# tinyusbboard.net
KiCad netlist of a schematic drawn in Altium Designer
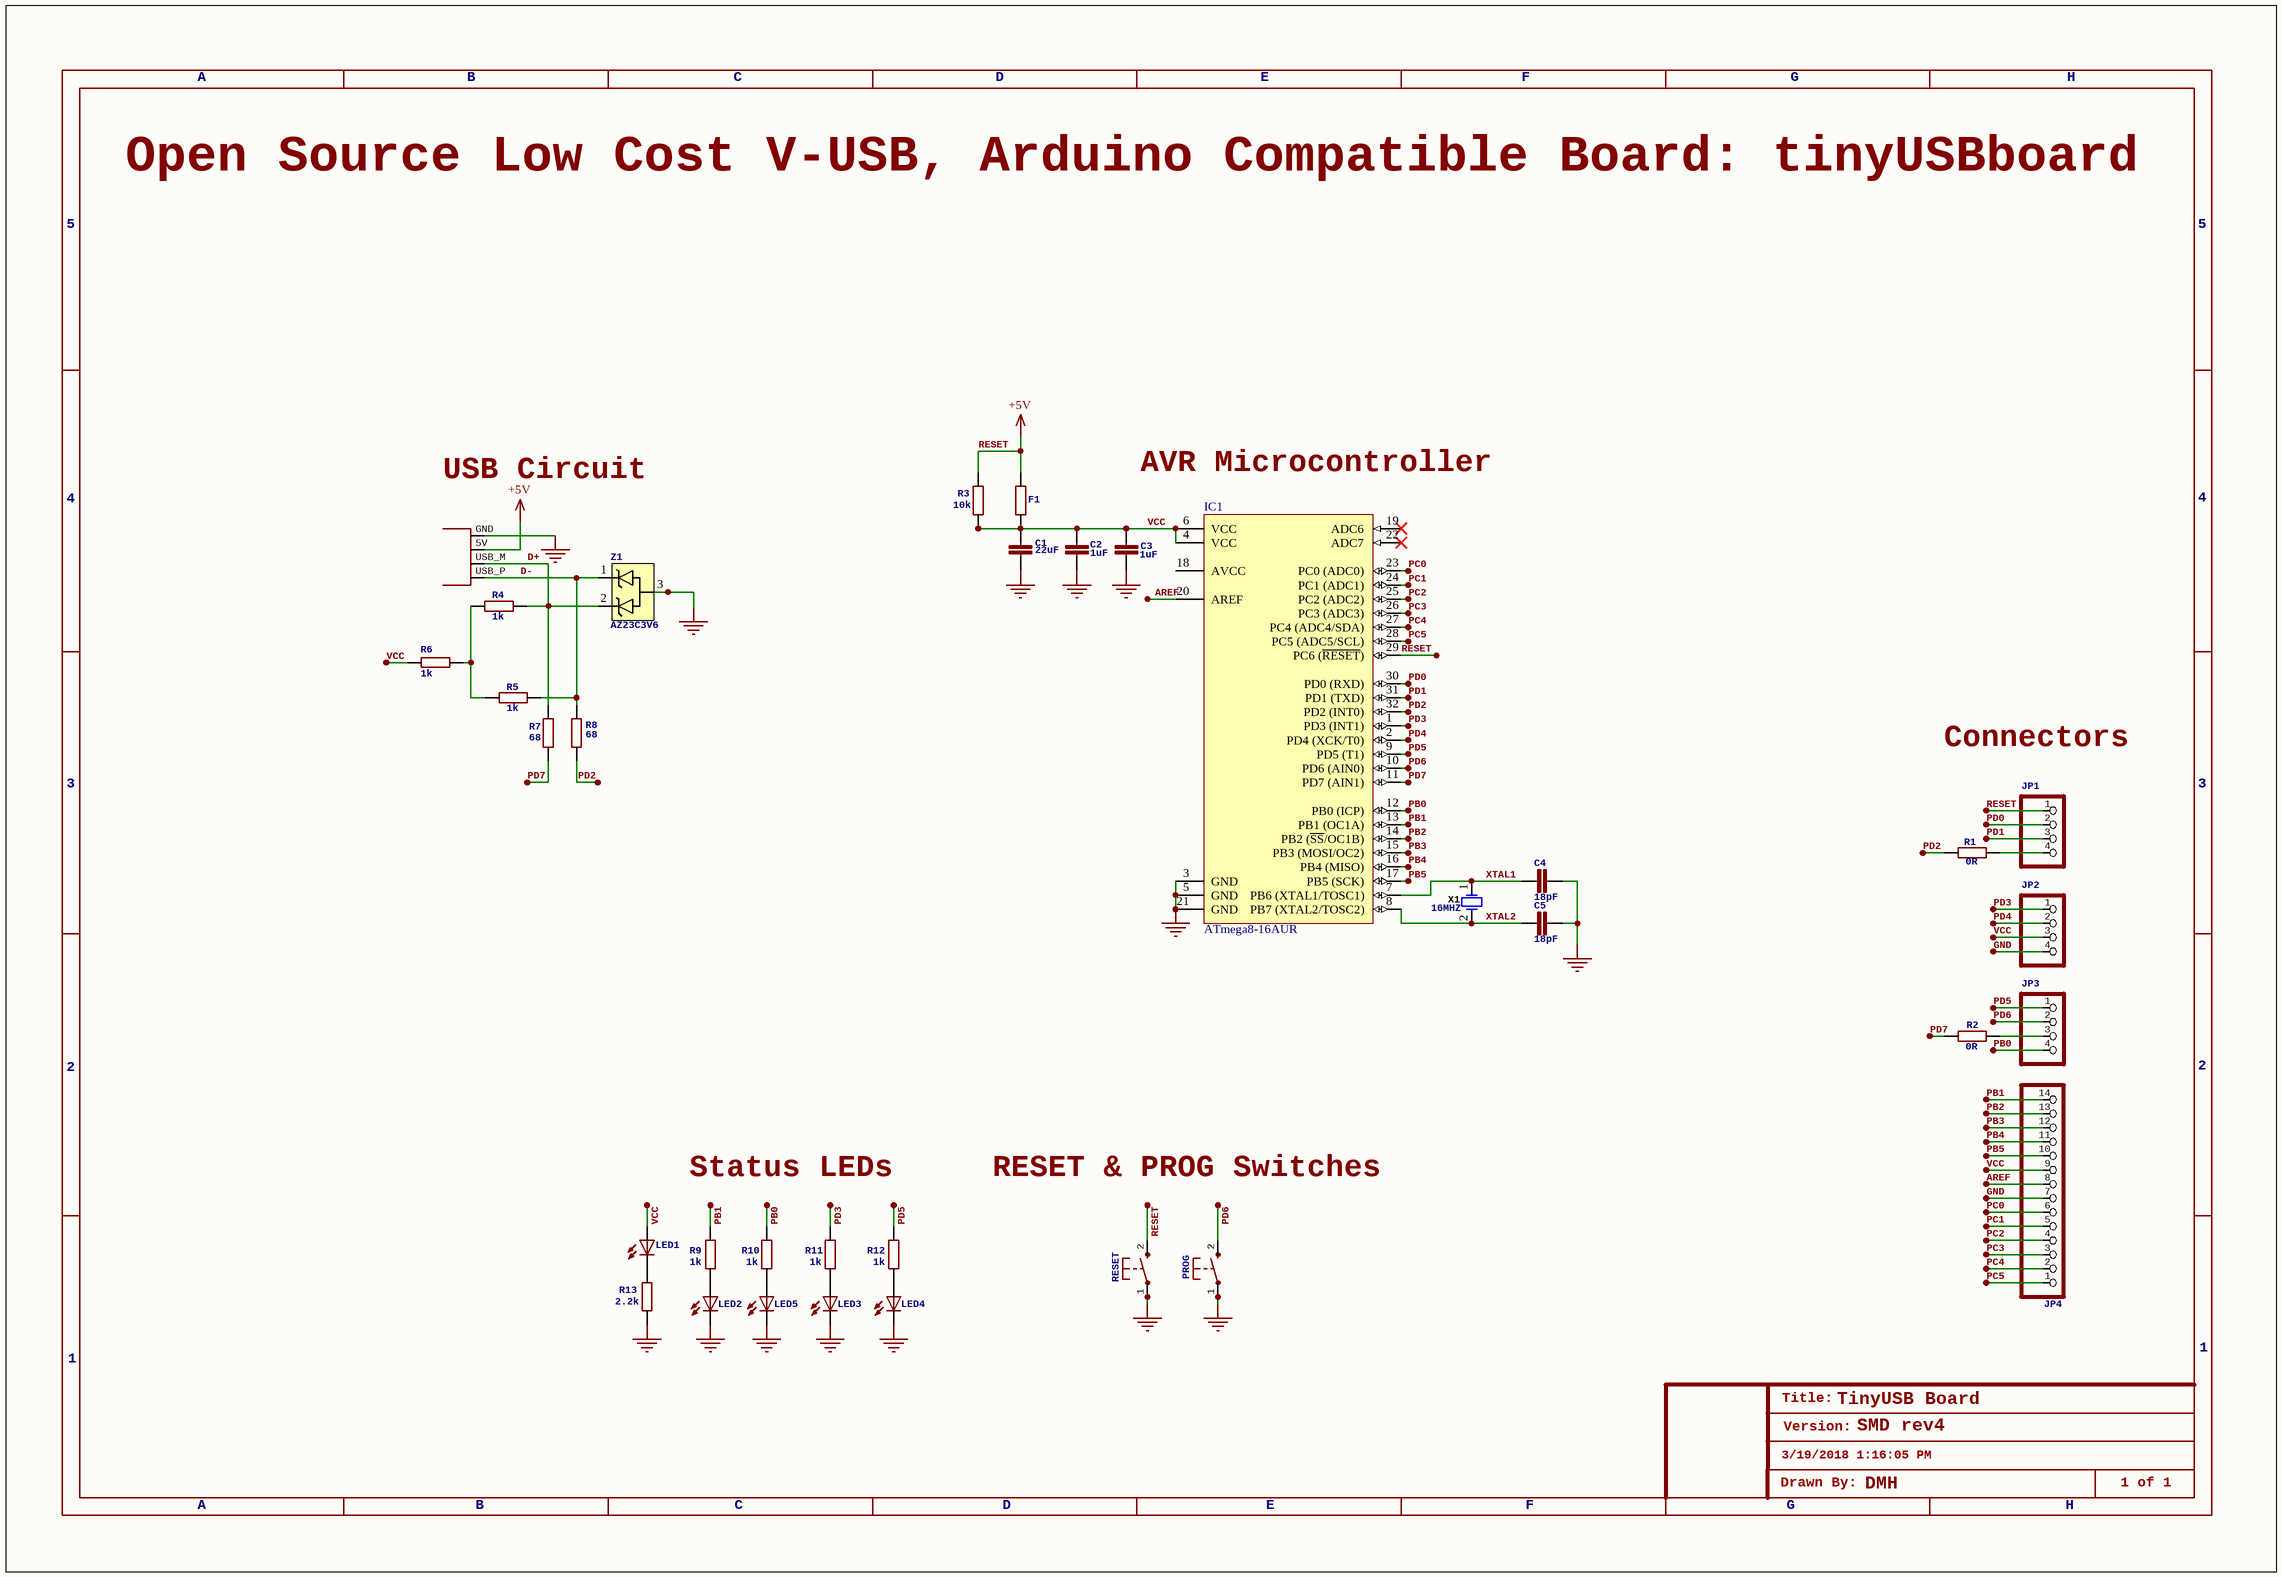
[diagram p0: tinyusbboard.SchDoc]

(export (version "E")
  (design (tool "Eeschema 10.0.6"))
  (components
    (comp (ref "C1")
      (value "22uF")
      (footprint "C1206K")
      (description "CAPACITOR, European symbol")
      (libsource (lib "resistor") (part "C-EUC1206K"))
    )
    (comp (ref "C2")
      (value "1uF")
      (footprint "C0805")
      (description "CAPACITOR, European symbol")
      (libsource (lib "") (part "C-EUC0805K_1"))
    )
    (comp (ref "C3")
      (value "1uF")
      (footprint "C0805")
      (description "CAPACITOR, European symbol")
      (libsource (lib "") (part "C-EUC0805K_1"))
    )
    (comp (ref "C4")
      (value "18pF")
      (footprint "C0805")
      (description "CAPACITOR, European symbol")
      (libsource (lib "resistor") (part "C-EUC0805K"))
    )
    (comp (ref "C5")
      (value "18pF")
      (footprint "C0805")
      (description "CAPACITOR, European symbol")
      (libsource (lib "resistor") (part "C-EUC0805K"))
    )
    (comp (ref "F1")
      (value "0")
      (footprint "R1206W")
      (description "RESISTOR, European symbol")
      (libsource (lib "resistor") (part "R-EU_R1206W"))
    )
    (comp (ref "IC1")
      (value "ATmega8-16AUR")
      (footprint "32A_M")
      (libsource (lib "Altium Content Vault") (part "MC-8B-AT8L-SQ32A"))
    )
    (comp (ref "JP1")
      (value "PINHD-1X4")
      (footprint "4P Jumper")
      (description "PIN HEADER")
      (libsource (lib "pinhead") (part "PINHD-1X4"))
    )
    (comp (ref "JP2")
      (value "PINHD-1X4")
      (footprint "4P Jumper")
      (description "PIN HEADER")
      (libsource (lib "pinhead") (part "PINHD-1X4"))
    )
    (comp (ref "JP3")
      (value "PINHD-1X4")
      (footprint "4P Jumper")
      (description "PIN HEADER")
      (libsource (lib "pinhead") (part "PINHD-1X4"))
    )
    (comp (ref "JP4")
      (value "PINHD-1X14")
      (footprint "124P Jumper")
      (description "PIN HEADER")
      (libsource (lib "pinhead") (part "PINHD-1X14"))
    )
    (comp (ref "LED1")
      (value "POWER")
      (footprint "LED_1206_2")
      (libsource (lib "led") (part "LEDCHIPLED_0805"))
    )
    (comp (ref "LED2")
      (value "red")
      (footprint "LED_1206_2")
      (libsource (lib "led") (part "LEDCHIPLED_0805"))
    )
    (comp (ref "LED3")
      (value "red")
      (footprint "LED_1206_2")
      (libsource (lib "led") (part "LEDCHIPLED_0805"))
    )
    (comp (ref "LED4")
      (value "red")
      (footprint "LED_1206_2")
      (libsource (lib "led") (part "LEDCHIPLED_0805"))
    )
    (comp (ref "LED5")
      (value "red")
      (footprint "LED_1206_2")
      (libsource (lib "led") (part "LEDCHIPLED_0805"))
    )
    (comp (ref "PROG")
      (value "KSS-2EG4430")
      (footprint "KSS-2EG4430")
      (libsource (lib "buttons") (part "KSS-2EG4430"))
    )
    (comp (ref "R1")
      (value "0R")
      (footprint "RESC0805(2012)_M")
      (description "RESISTOR, European symbol")
      (libsource (lib "resistor") (part "R-EU_R0805W"))
    )
    (comp (ref "R2")
      (value "0R")
      (footprint "RESC0805(2012)_M")
      (description "RESISTOR, European symbol")
      (libsource (lib "resistor") (part "R-EU_R0805W"))
    )
    (comp (ref "R3")
      (value "10k")
      (footprint "RESC0805(2012)_M")
      (description "RESISTOR, European symbol")
      (libsource (lib "resistor") (part "R-EU_R0805W"))
    )
    (comp (ref "R4")
      (value "1k")
      (footprint "RESC0805(2012)_M")
      (description "RESISTOR, European symbol")
      (libsource (lib "resistor") (part "R-EU_R0805W"))
    )
    (comp (ref "R5")
      (value "1k")
      (footprint "RESC0805(2012)_M")
      (description "RESISTOR, European symbol")
      (libsource (lib "resistor") (part "R-EU_R0805W"))
    )
    (comp (ref "R6")
      (value "1k")
      (footprint "RESC0805(2012)_M")
      (description "RESISTOR, European symbol")
      (libsource (lib "resistor") (part "R-EU_R0805W"))
    )
    (comp (ref "R7")
      (value "68")
      (footprint "RESC0805(2012)_M")
      (description "RESISTOR, European symbol")
      (libsource (lib "resistor") (part "R-EU_R0805W"))
    )
    (comp (ref "R8")
      (value "68")
      (footprint "RESC0805(2012)_M")
      (description "RESISTOR, European symbol")
      (libsource (lib "resistor") (part "R-EU_R0805W"))
    )
    (comp (ref "R9")
      (value "1k")
      (footprint "RESC0805(2012)_M")
      (description "RESISTOR, European symbol")
      (libsource (lib "resistor") (part "R-EU_R0805W"))
    )
    (comp (ref "R10")
      (value "1k")
      (footprint "RESC0805(2012)_M")
      (description "RESISTOR, European symbol")
      (libsource (lib "resistor") (part "R-EU_R0805W"))
    )
    (comp (ref "R11")
      (value "1k")
      (footprint "RESC0805(2012)_M")
      (description "RESISTOR, European symbol")
      (libsource (lib "resistor") (part "R-EU_R0805W"))
    )
    (comp (ref "R12")
      (value "1k")
      (footprint "RESC0805(2012)_M")
      (description "RESISTOR, European symbol")
      (libsource (lib "resistor") (part "R-EU_R0805W"))
    )
    (comp (ref "R13")
      (value "2.2k")
      (footprint "RESC0805(2012)_M")
      (description "RESISTOR, European symbol")
      (libsource (lib "resistor") (part "R-EU_R0805W"))
    )
    (comp (ref "RESET")
      (value "KSS-2EG4430")
      (footprint "KSS-2EG4430")
      (libsource (lib "buttons") (part "KSS-2EG4430"))
    )
    (comp (ref "USB") (value "USBPCB") (footprint "USB-A-PCB") (libsource (lib "SparkFun") (part "USBPCB")))
    (comp (ref "X1")
      (value "16MHZ")
      (footprint "JPY-HC-49US")
      (description "Crystal, 16 MHz, +/- 30 ppm, 18 pF, -20 to 70 degC, 2-Pin THD")
      (fields (field (name "MANUFACTURER") "Jing peng yuan"))
      (libsource (lib "Crystal_HC-49S") (part "CMP-2100-03645-1"))
    )
    (comp (ref "Z1")
      (value "AZ23C3V6")
      (footprint "SOT23_M")
      (description "3.6V Zener Diode, Dual Common Anode")
      (fields (field (name "MANUFACTURER") "Vishay Semi"))
      (libsource (lib "tinyusbboard") (part "DUAL_ZENER"))
    )
  )
  (nets
    (net (code "1") (name "+5V") (class "Default")
      (node (ref "F1") (pin "1") (pinfunction "1_1") (pintype "passive"))
      (node (ref "IC1") (pin "29") (pinfunction "PC6_(~{RESET})_29") (pintype "bidirectional"))
      (node (ref "JP1") (pin "1") (pinfunction "1_1") (pintype "passive"))
      (node (ref "R3") (pin "1") (pinfunction "1_1") (pintype "passive"))
      (node (ref "RESET") (pin "2") (pinfunction "S_2") (pintype "passive"))
      (node (ref "USB") (pin "5V") (pinfunction "VBUS_5V") (pintype "passive"))
    )
    (net (code "2") (name "/AREF") (class "Default")
      (node (ref "IC1") (pin "20") (pinfunction "AREF_20") (pintype "passive"))
      (node (ref "JP4") (pin "8") (pinfunction "8_8") (pintype "passive"))
    )
    (net (code "3") (name "/D+") (class "Default")
      (node (ref "R4") (pin "2") (pinfunction "2_2") (pintype "passive"))
      (node (ref "R7") (pin "2") (pinfunction "2_2") (pintype "passive"))
      (node (ref "USB") (pin "USB_M") (pinfunction "D-_USB_M") (pintype "passive"))
      (node (ref "Z1") (pin "2") (pinfunction "2_2") (pintype "passive"))
    )
    (net (code "4") (name "/D-") (class "Default")
      (node (ref "R5") (pin "2") (pinfunction "2_2") (pintype "passive"))
      (node (ref "R8") (pin "2") (pinfunction "2_2") (pintype "passive"))
      (node (ref "USB") (pin "USB_P") (pinfunction "D+_USB_P") (pintype "passive"))
      (node (ref "Z1") (pin "1") (pinfunction "1_1") (pintype "passive"))
    )
    (net (code "5") (name "/PB0") (class "Default")
      (node (ref "IC1") (pin "12") (pinfunction "PB0_(ICP)_12") (pintype "bidirectional"))
      (node (ref "JP3") (pin "4") (pinfunction "4_4") (pintype "passive"))
      (node (ref "R10") (pin "1") (pinfunction "1_1") (pintype "passive"))
    )
    (net (code "6") (name "/PB1") (class "Default")
      (node (ref "IC1") (pin "13") (pinfunction "PB1_(OC1A)_13") (pintype "bidirectional"))
      (node (ref "JP4") (pin "14") (pinfunction "14_14") (pintype "passive"))
      (node (ref "R9") (pin "1") (pinfunction "1_1") (pintype "passive"))
    )
    (net (code "7") (name "/PB2") (class "Default")
      (node (ref "IC1") (pin "14") (pinfunction "PB2_(~{SS}/OC1B)_14") (pintype "bidirectional"))
      (node (ref "JP4") (pin "13") (pinfunction "13_13") (pintype "passive"))
    )
    (net (code "8") (name "/PB3") (class "Default")
      (node (ref "IC1") (pin "15") (pinfunction "PB3_(MOSI/OC2)_15") (pintype "bidirectional"))
      (node (ref "JP4") (pin "12") (pinfunction "12_12") (pintype "passive"))
    )
    (net (code "9") (name "/PB4") (class "Default")
      (node (ref "IC1") (pin "16") (pinfunction "PB4_(MISO)_16") (pintype "bidirectional"))
      (node (ref "JP4") (pin "11") (pinfunction "11_11") (pintype "passive"))
    )
    (net (code "10") (name "/PB5") (class "Default")
      (node (ref "IC1") (pin "17") (pinfunction "PB5_(SCK)_17") (pintype "bidirectional"))
      (node (ref "JP4") (pin "10") (pinfunction "10_10") (pintype "passive"))
    )
    (net (code "11") (name "/PC0") (class "Default")
      (node (ref "IC1") (pin "23") (pinfunction "PC0_(ADC0)_23") (pintype "bidirectional"))
      (node (ref "JP4") (pin "6") (pinfunction "6_6") (pintype "passive"))
    )
    (net (code "12") (name "/PC1") (class "Default")
      (node (ref "IC1") (pin "24") (pinfunction "PC1_(ADC1)_24") (pintype "bidirectional"))
      (node (ref "JP4") (pin "5") (pinfunction "5_5") (pintype "passive"))
    )
    (net (code "13") (name "/PC2") (class "Default")
      (node (ref "IC1") (pin "25") (pinfunction "PC2_(ADC2)_25") (pintype "bidirectional"))
      (node (ref "JP4") (pin "4") (pinfunction "4_4") (pintype "passive"))
    )
    (net (code "14") (name "/PC3") (class "Default")
      (node (ref "IC1") (pin "26") (pinfunction "PC3_(ADC3)_26") (pintype "bidirectional"))
      (node (ref "JP4") (pin "3") (pinfunction "3_3") (pintype "passive"))
    )
    (net (code "15") (name "/PC4") (class "Default")
      (node (ref "IC1") (pin "27") (pinfunction "PC4_(ADC4/SDA)_27") (pintype "bidirectional"))
      (node (ref "JP4") (pin "2") (pinfunction "2_2") (pintype "passive"))
    )
    (net (code "16") (name "/PC5") (class "Default")
      (node (ref "IC1") (pin "28") (pinfunction "PC5_(ADC5/SCL)_28") (pintype "bidirectional"))
      (node (ref "JP4") (pin "1") (pinfunction "1_1") (pintype "passive"))
    )
    (net (code "17") (name "/PD0") (class "Default")
      (node (ref "IC1") (pin "30") (pinfunction "PD0_(RXD)_30") (pintype "bidirectional"))
      (node (ref "JP1") (pin "2") (pinfunction "2_2") (pintype "passive"))
    )
    (net (code "18") (name "/PD1") (class "Default")
      (node (ref "IC1") (pin "31") (pinfunction "PD1_(TXD)_31") (pintype "bidirectional"))
      (node (ref "JP1") (pin "3") (pinfunction "3_3") (pintype "passive"))
    )
    (net (code "19") (name "/PD2") (class "Default")
      (node (ref "IC1") (pin "32") (pinfunction "PD2_(INT0)_32") (pintype "bidirectional"))
      (node (ref "R1") (pin "1") (pinfunction "1_1") (pintype "passive"))
      (node (ref "R8") (pin "1") (pinfunction "1_1") (pintype "passive"))
    )
    (net (code "20") (name "/PD3") (class "Default")
      (node (ref "IC1") (pin "1") (pinfunction "PD3_(INT1)_1") (pintype "bidirectional"))
      (node (ref "JP2") (pin "1") (pinfunction "1_1") (pintype "passive"))
      (node (ref "R11") (pin "1") (pinfunction "1_1") (pintype "passive"))
    )
    (net (code "21") (name "/PD4") (class "Default")
      (node (ref "IC1") (pin "2") (pinfunction "PD4_(XCK/T0)_2") (pintype "bidirectional"))
      (node (ref "JP2") (pin "2") (pinfunction "2_2") (pintype "passive"))
    )
    (net (code "22") (name "/PD5") (class "Default")
      (node (ref "IC1") (pin "9") (pinfunction "PD5_(T1)_9") (pintype "bidirectional"))
      (node (ref "JP3") (pin "1") (pinfunction "1_1") (pintype "passive"))
      (node (ref "R12") (pin "1") (pinfunction "1_1") (pintype "passive"))
    )
    (net (code "23") (name "/PD6") (class "Default")
      (node (ref "IC1") (pin "10") (pinfunction "PD6_(AIN0)_10") (pintype "bidirectional"))
      (node (ref "JP3") (pin "2") (pinfunction "2_2") (pintype "passive"))
      (node (ref "PROG") (pin "2") (pinfunction "S_2") (pintype "passive"))
    )
    (net (code "24") (name "/PD7") (class "Default")
      (node (ref "IC1") (pin "11") (pinfunction "PD7_(AIN1)_11") (pintype "bidirectional"))
      (node (ref "R2") (pin "1") (pinfunction "1_1") (pintype "passive"))
      (node (ref "R7") (pin "1") (pinfunction "1_1") (pintype "passive"))
    )
    (net (code "25") (name "/VCC") (class "Default")
      (node (ref "C1") (pin "1") (pinfunction "1_1") (pintype "passive"))
      (node (ref "C2") (pin "1") (pinfunction "1_1") (pintype "passive"))
      (node (ref "C3") (pin "1") (pinfunction "1_1") (pintype "passive"))
      (node (ref "F1") (pin "2") (pinfunction "2_2") (pintype "passive"))
      (node (ref "IC1") (pin "4") (pinfunction "VCC_4") (pintype "power_in"))
      (node (ref "IC1") (pin "6") (pinfunction "VCC_6") (pintype "power_in"))
      (node (ref "JP2") (pin "3") (pinfunction "3_3") (pintype "passive"))
      (node (ref "JP4") (pin "9") (pinfunction "9_9") (pintype "passive"))
      (node (ref "LED1") (pin "A") (pinfunction "A_A") (pintype "passive"))
      (node (ref "R3") (pin "2") (pinfunction "2_2") (pintype "passive"))
      (node (ref "R6") (pin "2") (pinfunction "2_2") (pintype "passive"))
    )
    (net (code "26") (name "/XTAL1") (class "Default")
      (node (ref "C4") (pin "1") (pinfunction "1_1") (pintype "passive"))
      (node (ref "IC1") (pin "7") (pinfunction "PB6_(XTAL1/TOSC1)_7") (pintype "bidirectional"))
      (node (ref "X1") (pin "1") (pinfunction "1_1") (pintype "passive"))
    )
    (net (code "27") (name "/XTAL2") (class "Default")
      (node (ref "C5") (pin "1") (pinfunction "1_1") (pintype "passive"))
      (node (ref "IC1") (pin "8") (pinfunction "PB7_(XTAL2/TOSC2)_8") (pintype "bidirectional"))
      (node (ref "X1") (pin "2") (pinfunction "2_2") (pintype "passive"))
    )
    (net (code "28") (name "GND") (class "Default")
      (node (ref "C1") (pin "2") (pinfunction "2_2") (pintype "passive"))
      (node (ref "C2") (pin "2") (pinfunction "2_2") (pintype "passive"))
      (node (ref "C3") (pin "2") (pinfunction "2_2") (pintype "passive"))
      (node (ref "C4") (pin "2") (pinfunction "2_2") (pintype "passive"))
      (node (ref "C5") (pin "2") (pinfunction "2_2") (pintype "passive"))
      (node (ref "IC1") (pin "21") (pinfunction "GND_21") (pintype "power_in"))
      (node (ref "IC1") (pin "3") (pinfunction "GND_3") (pintype "power_in"))
      (node (ref "IC1") (pin "5") (pinfunction "GND_5") (pintype "power_in"))
      (node (ref "JP2") (pin "4") (pinfunction "4_4") (pintype "passive"))
      (node (ref "JP4") (pin "7") (pinfunction "7_7") (pintype "passive"))
      (node (ref "LED2") (pin "C") (pinfunction "C_C") (pintype "passive"))
      (node (ref "LED3") (pin "C") (pinfunction "C_C") (pintype "passive"))
      (node (ref "LED4") (pin "C") (pinfunction "C_C") (pintype "passive"))
      (node (ref "LED5") (pin "C") (pinfunction "C_C") (pintype "passive"))
      (node (ref "PROG") (pin "1") (pinfunction "P_1") (pintype "passive"))
      (node (ref "R13") (pin "2") (pinfunction "2_2") (pintype "passive"))
      (node (ref "RESET") (pin "1") (pinfunction "P_1") (pintype "passive"))
      (node (ref "USB") (pin "GND") (pinfunction "GND_GND") (pintype "passive"))
      (node (ref "Z1") (pin "3") (pinfunction "3_3") (pintype "passive"))
    )
    (net (code "29") (name "Net-(JP1-Pad4)") (class "Default")
      (node (ref "JP1") (pin "4") (pinfunction "4_4") (pintype "passive"))
      (node (ref "R1") (pin "2") (pinfunction "2_2") (pintype "passive"))
    )
    (net (code "30") (name "Net-(JP3-Pad3)") (class "Default")
      (node (ref "JP3") (pin "3") (pinfunction "3_3") (pintype "passive"))
      (node (ref "R2") (pin "2") (pinfunction "2_2") (pintype "passive"))
    )
    (net (code "31") (name "Net-(LED1-PadC)") (class "Default")
      (node (ref "LED1") (pin "C") (pinfunction "C_C") (pintype "passive"))
      (node (ref "R13") (pin "1") (pinfunction "1_1") (pintype "passive"))
    )
    (net (code "32") (name "Net-(LED2-PadA)") (class "Default")
      (node (ref "LED2") (pin "A") (pinfunction "A_A") (pintype "passive"))
      (node (ref "R9") (pin "2") (pinfunction "2_2") (pintype "passive"))
    )
    (net (code "33") (name "Net-(LED3-PadA)") (class "Default")
      (node (ref "LED3") (pin "A") (pinfunction "A_A") (pintype "passive"))
      (node (ref "R11") (pin "2") (pinfunction "2_2") (pintype "passive"))
    )
    (net (code "34") (name "Net-(LED4-PadA)") (class "Default")
      (node (ref "LED4") (pin "A") (pinfunction "A_A") (pintype "passive"))
      (node (ref "R12") (pin "2") (pinfunction "2_2") (pintype "passive"))
    )
    (net (code "35") (name "Net-(LED5-PadA)") (class "Default")
      (node (ref "LED5") (pin "A") (pinfunction "A_A") (pintype "passive"))
      (node (ref "R10") (pin "2") (pinfunction "2_2") (pintype "passive"))
    )
    (net (code "36") (name "Net-(R4-Pad1)") (class "Default")
      (node (ref "R4") (pin "1") (pinfunction "1_1") (pintype "passive"))
      (node (ref "R5") (pin "1") (pinfunction "1_1") (pintype "passive"))
      (node (ref "R6") (pin "1") (pinfunction "1_1") (pintype "passive"))
    )
    (net (code "37") (name "unconnected-(IC1-ADC6-Pad19)") (class "Default")
      (node (ref "IC1") (pin "19") (pinfunction "ADC6_19") (pintype "input+no_connect"))
    )
    (net (code "38") (name "unconnected-(IC1-ADC7-Pad22)") (class "Default")
      (node (ref "IC1") (pin "22") (pinfunction "ADC7_22") (pintype "input+no_connect"))
    )
    (net (code "39") (name "unconnected-(IC1-AVCC-Pad18)") (class "Default")
      (node (ref "IC1") (pin "18") (pinfunction "AVCC_18") (pintype "power_in"))
    )
  )
)
